# CampLight.net
KiCad netlist of a schematic drawn in EAGLE
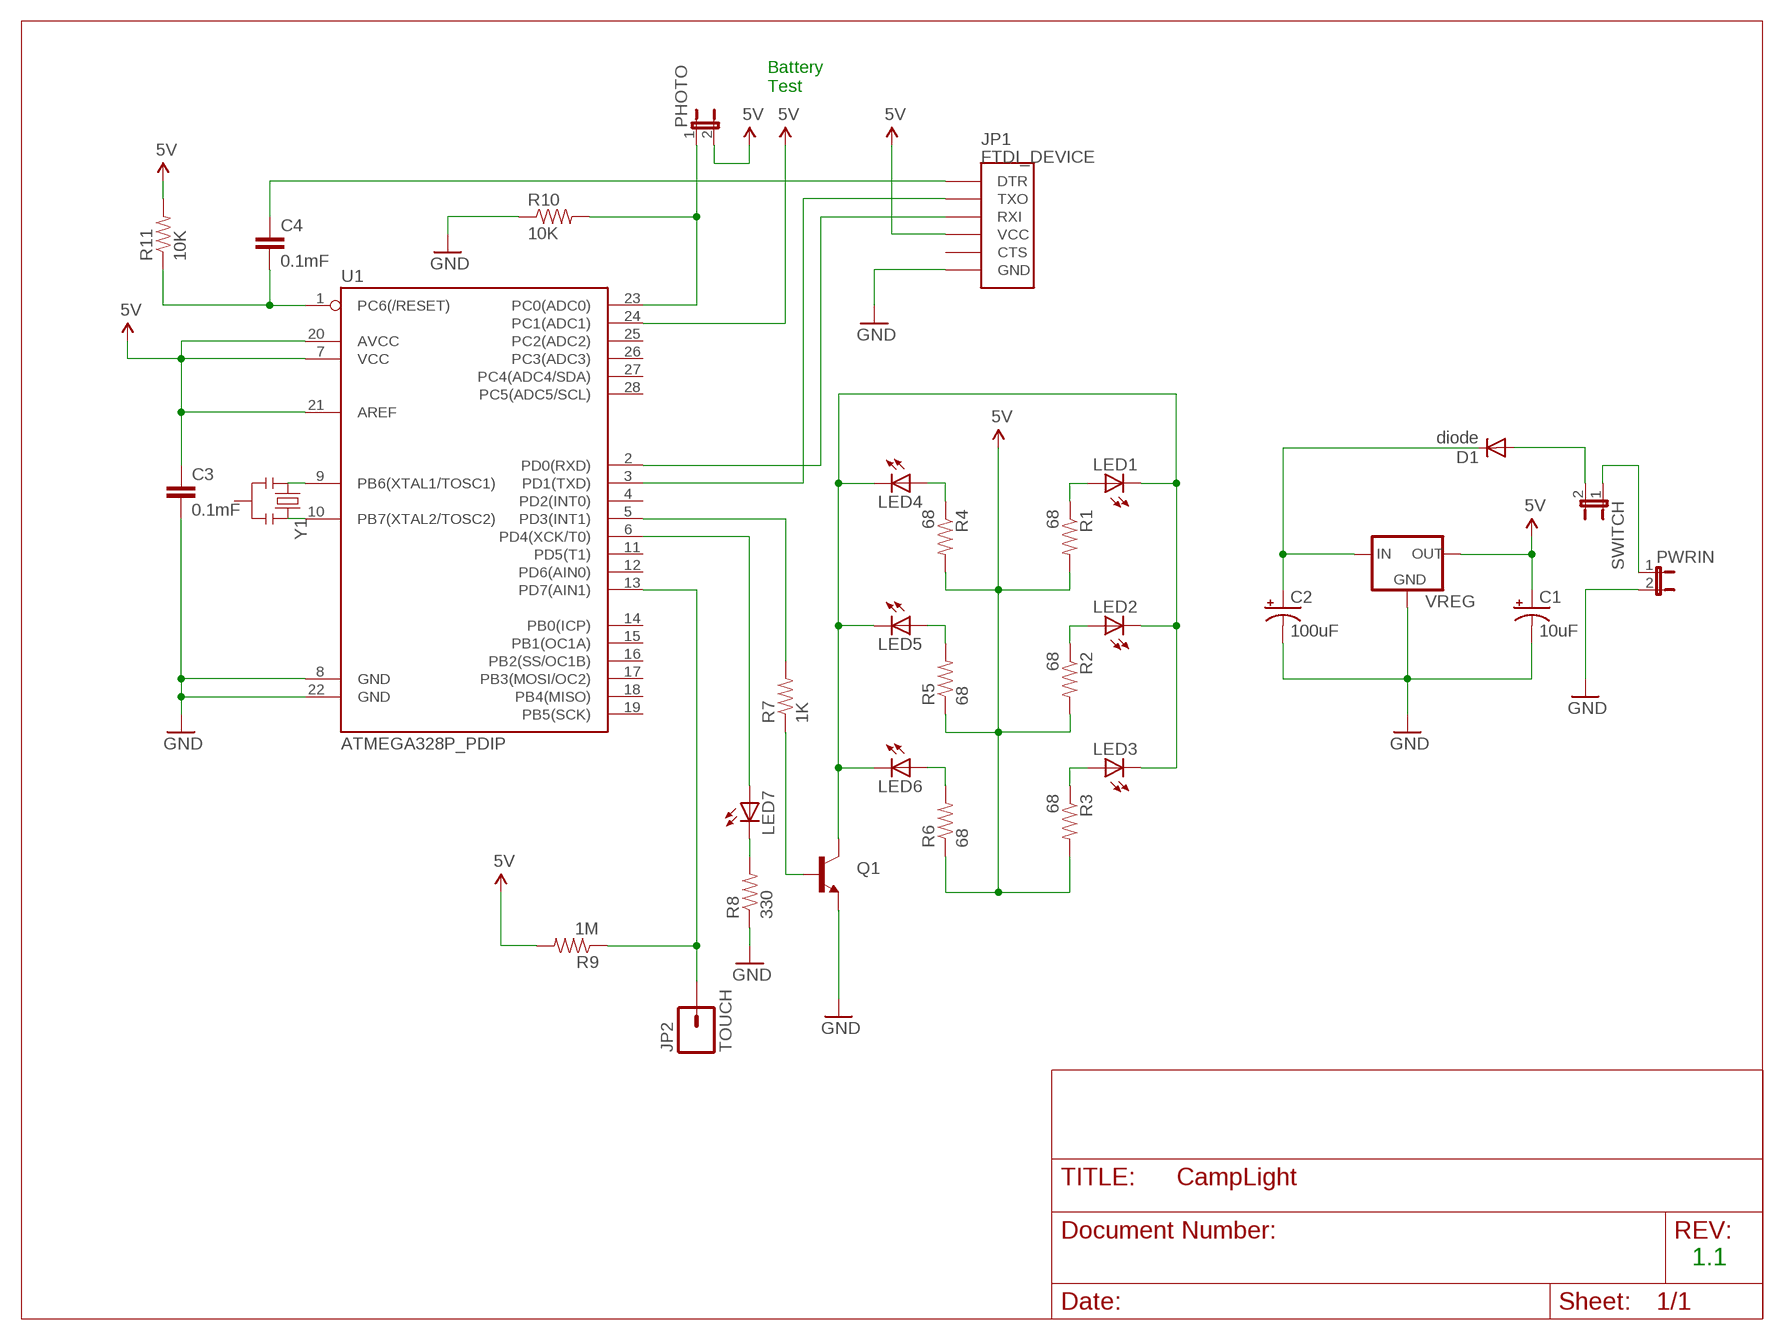
[diagram p0: schematic, sheet 1]

(export (version "E")
  (design (tool "Eeschema 10.0.6"))
  (components
    (comp (ref "C1")
      (value "10uF")
      (footprint "eagle-import:CPOL-RADIAL-10UF-25V")
      (libsource (lib "eagle-import") (part "CAP_POLPTH2"))
    )
    (comp (ref "C2")
      (value "100uF")
      (footprint "eagle-import:CPOL-RADIAL-10UF-25V")
      (libsource (lib "eagle-import") (part "CAP_POLPTH2"))
    )
    (comp (ref "C3")
      (value "0.1mF")
      (footprint "eagle-import:CAP-PTH-SMALL")
      (libsource (lib "eagle-import") (part "CAPPTH"))
    )
    (comp (ref "C4")
      (value "0.1mF")
      (footprint "eagle-import:CAP-PTH-SMALL")
      (libsource (lib "eagle-import") (part "CAPPTH"))
    )
    (comp (ref "D1")
      (value "diode")
      (footprint "eagle-import:DIODE-1N4001")
      (libsource (lib "eagle-import") (part "DIODEPTH"))
    )
    (comp (ref "JP1")
      (value "FTDI_DEVICE")
      (footprint "eagle-import:FTDI_DEVICE_SIDE")
      (libsource (lib "eagle-import") (part "FTDI_DEVICE"))
    )
    (comp (ref "JP2")
      (value "TOUCH")
      (footprint "eagle-import:1X01")
      (libsource (lib "eagle-import") (part "M01PTH"))
    )
    (comp (ref "LED1")
      (value "LED5MM")
      (footprint "eagle-import:LED5MM")
      (libsource (lib "eagle-import") (part "LED5MM"))
    )
    (comp (ref "LED2")
      (value "LED5MM")
      (footprint "eagle-import:LED5MM")
      (libsource (lib "eagle-import") (part "LED5MM"))
    )
    (comp (ref "LED3")
      (value "LED5MM")
      (footprint "eagle-import:LED5MM")
      (libsource (lib "eagle-import") (part "LED5MM"))
    )
    (comp (ref "LED4")
      (value "LED5MM")
      (footprint "eagle-import:LED5MM")
      (libsource (lib "eagle-import") (part "LED5MM"))
    )
    (comp (ref "LED5")
      (value "LED5MM")
      (footprint "eagle-import:LED5MM")
      (libsource (lib "eagle-import") (part "LED5MM"))
    )
    (comp (ref "LED6")
      (value "LED5MM")
      (footprint "eagle-import:LED5MM")
      (libsource (lib "eagle-import") (part "LED5MM"))
    )
    (comp (ref "LED7")
      (value "LED3MM")
      (footprint "eagle-import:LED3MM")
      (libsource (lib "eagle-import") (part "LED3MM"))
    )
    (comp (ref "PHOTO")
      (value "JUMPER-2PTH_LOCK")
      (footprint "eagle-import:1X02_LOCK")
      (libsource (lib "eagle-import") (part "JUMPER-2PTH_LOCK"))
    )
    (comp (ref "PWRIN")
      (value "JUMPER-2PTH_LOCK")
      (footprint "eagle-import:1X02_LOCK")
      (libsource (lib "eagle-import") (part "JUMPER-2PTH_LOCK"))
    )
    (comp (ref "Q1")
      (value "TRANSISTOR_NPNTO-92-AMMO")
      (footprint "eagle-import:TO-92-AMMO")
      (libsource (lib "eagle-import") (part "TRANSISTOR_NPNTO-92-AMMO"))
    )
    (comp (ref "R1")
      (value "68")
      (footprint "eagle-import:AXIAL-0.3")
      (libsource (lib "eagle-import") (part "SparkFun-Resistors_RESISTORAXIAL-0.3"))
    )
    (comp (ref "R2")
      (value "68")
      (footprint "eagle-import:AXIAL-0.3")
      (libsource (lib "eagle-import") (part "SparkFun-Resistors_RESISTORAXIAL-0.3"))
    )
    (comp (ref "R3")
      (value "68")
      (footprint "eagle-import:AXIAL-0.3")
      (libsource (lib "eagle-import") (part "SparkFun-Resistors_RESISTORAXIAL-0.3"))
    )
    (comp (ref "R4")
      (value "68")
      (footprint "eagle-import:AXIAL-0.3")
      (libsource (lib "eagle-import") (part "SparkFun-Resistors_RESISTORAXIAL-0.3"))
    )
    (comp (ref "R5")
      (value "68")
      (footprint "eagle-import:AXIAL-0.3")
      (libsource (lib "eagle-import") (part "SparkFun-Resistors_RESISTORAXIAL-0.3"))
    )
    (comp (ref "R6")
      (value "68")
      (footprint "eagle-import:AXIAL-0.3")
      (libsource (lib "eagle-import") (part "SparkFun-Resistors_RESISTORAXIAL-0.3"))
    )
    (comp (ref "R7")
      (value "1K")
      (footprint "eagle-import:AXIAL-0.4")
      (libsource (lib "eagle-import") (part "RESISTORPTH-1/4W"))
    )
    (comp (ref "R8")
      (value "330")
      (footprint "eagle-import:AXIAL-0.3")
      (libsource (lib "eagle-import") (part "SparkFun-Resistors_RESISTORAXIAL-0.3"))
    )
    (comp (ref "R9")
      (value "1M")
      (footprint "eagle-import:AXIAL-0.4")
      (libsource (lib "eagle-import") (part "RESISTORPTH-1/4W"))
    )
    (comp (ref "R10")
      (value "10K")
      (footprint "eagle-import:AXIAL-0.3")
      (libsource (lib "eagle-import") (part "SparkFun-Resistors_RESISTORAXIAL-0.3"))
    )
    (comp (ref "R11")
      (value "10K")
      (footprint "eagle-import:AXIAL-0.3")
      (libsource (lib "eagle-import") (part "SparkFun-Resistors_RESISTORAXIAL-0.3"))
    )
    (comp (ref "SWITCH")
      (value "JUMPER-2PTH_LOCK")
      (footprint "eagle-import:1X02_LOCK")
      (libsource (lib "eagle-import") (part "JUMPER-2PTH_LOCK"))
    )
    (comp (ref "U1")
      (value "ATMEGA328P_PDIP")
      (footprint "eagle-import:DIL28-3")
      (libsource (lib "eagle-import") (part "ATMEGA328P_PDIP"))
    )
    (comp (ref "VREG")
      (value "78LXX")
      (footprint "eagle-import:78LXX")
      (libsource (lib "eagle-import") (part "78LXX"))
    )
    (comp (ref "Y1")
      (value "RESONATORPTH")
      (footprint "eagle-import:RESONATOR-PTH")
      (libsource (lib "eagle-import") (part "RESONATORPTH"))
    )
  )
  (nets
    (net (code "1") (name "5V") (class "Default")
      (node (ref "C1") (pin "1") (pinfunction "+_1") (pintype "passive"))
      (node (ref "C3") (pin "1") (pinfunction "1_1") (pintype "passive"))
      (node (ref "JP1") (pin "P$4") (pinfunction "VCC_P$4") (pintype "bidirectional"))
      (node (ref "PHOTO") (pin "2") (pinfunction "2_2") (pintype "passive"))
      (node (ref "R1") (pin "P$2") (pinfunction "2_P$2") (pintype "passive"))
      (node (ref "R11") (pin "P$2") (pinfunction "2_P$2") (pintype "passive"))
      (node (ref "R2") (pin "P$2") (pinfunction "2_P$2") (pintype "passive"))
      (node (ref "R3") (pin "P$2") (pinfunction "2_P$2") (pintype "passive"))
      (node (ref "R4") (pin "P$2") (pinfunction "2_P$2") (pintype "passive"))
      (node (ref "R5") (pin "P$1") (pinfunction "1_P$1") (pintype "passive"))
      (node (ref "R6") (pin "P$1") (pinfunction "1_P$1") (pintype "passive"))
      (node (ref "R9") (pin "P$2") (pinfunction "2_P$2") (pintype "passive"))
      (node (ref "U1") (pin "20") (pinfunction "AVCC_20") (pintype "bidirectional"))
      (node (ref "U1") (pin "21") (pinfunction "AREF_21") (pintype "bidirectional"))
      (node (ref "U1") (pin "24") (pinfunction "PC1(ADC1)_24") (pintype "bidirectional"))
      (node (ref "U1") (pin "7") (pinfunction "VCC_7") (pintype "bidirectional"))
      (node (ref "VREG") (pin "OUT") (pinfunction "OUT_OUT") (pintype "passive"))
    )
    (net (code "2") (name "GND") (class "Default")
      (node (ref "C1") (pin "2") (pinfunction "-_2") (pintype "passive"))
      (node (ref "C2") (pin "2") (pinfunction "-_2") (pintype "passive"))
      (node (ref "C3") (pin "2") (pinfunction "2_2") (pintype "passive"))
      (node (ref "JP1") (pin "P$6") (pinfunction "GND_P$6") (pintype "bidirectional"))
      (node (ref "PWRIN") (pin "2") (pinfunction "2_2") (pintype "passive"))
      (node (ref "Q1") (pin "1") (pinfunction "E_1") (pintype "passive"))
      (node (ref "R10") (pin "P$1") (pinfunction "1_P$1") (pintype "passive"))
      (node (ref "R8") (pin "P$1") (pinfunction "1_P$1") (pintype "passive"))
      (node (ref "U1") (pin "22") (pinfunction "GND_22") (pintype "bidirectional"))
      (node (ref "U1") (pin "8") (pinfunction "GND_8") (pintype "bidirectional"))
      (node (ref "VREG") (pin "GND") (pinfunction "GND_GND") (pintype "input"))
    )
    (net (code "3") (name "Net-(C2-+)") (class "Default")
      (node (ref "C2") (pin "1") (pinfunction "+_1") (pintype "passive"))
      (node (ref "D1") (pin "C") (pinfunction "C_C") (pintype "passive"))
      (node (ref "VREG") (pin "IN") (pinfunction "IN_IN") (pintype "input"))
    )
    (net (code "4") (name "Net-(D1-PadA)") (class "Default")
      (node (ref "D1") (pin "A") (pinfunction "A_A") (pintype "passive"))
      (node (ref "SWITCH") (pin "2") (pinfunction "2_2") (pintype "passive"))
    )
    (net (code "5") (name "Net-(JP1-DTR)") (class "Default")
      (node (ref "C4") (pin "1") (pinfunction "1_1") (pintype "passive"))
      (node (ref "JP1") (pin "P$1") (pinfunction "DTR_P$1") (pintype "bidirectional"))
    )
    (net (code "6") (name "Net-(JP1-RXI)") (class "Default")
      (node (ref "JP1") (pin "P$3") (pinfunction "RXI_P$3") (pintype "bidirectional"))
      (node (ref "U1") (pin "2") (pinfunction "PD0(RXD)_2") (pintype "bidirectional"))
    )
    (net (code "7") (name "Net-(JP1-TXO)") (class "Default")
      (node (ref "JP1") (pin "P$2") (pinfunction "TXO_P$2") (pintype "bidirectional"))
      (node (ref "U1") (pin "3") (pinfunction "PD1(TXD)_3") (pintype "bidirectional"))
    )
    (net (code "8") (name "Net-(LED1-C)") (class "Default")
      (node (ref "LED1") (pin "K") (pinfunction "C_K") (pintype "passive"))
      (node (ref "LED2") (pin "K") (pinfunction "C_K") (pintype "passive"))
      (node (ref "LED3") (pin "K") (pinfunction "C_K") (pintype "passive"))
      (node (ref "LED4") (pin "K") (pinfunction "C_K") (pintype "passive"))
      (node (ref "LED5") (pin "K") (pinfunction "C_K") (pintype "passive"))
      (node (ref "LED6") (pin "K") (pinfunction "C_K") (pintype "passive"))
      (node (ref "Q1") (pin "3") (pinfunction "C_3") (pintype "passive"))
    )
    (net (code "9") (name "Net-(LED7-C)") (class "Default")
      (node (ref "LED7") (pin "K") (pinfunction "C_K") (pintype "passive"))
      (node (ref "R8") (pin "P$2") (pinfunction "2_P$2") (pintype "passive"))
    )
    (net (code "10") (name "Net-(PWRIN-Pad1)") (class "Default")
      (node (ref "PWRIN") (pin "1") (pinfunction "1_1") (pintype "passive"))
      (node (ref "SWITCH") (pin "1") (pinfunction "1_1") (pintype "passive"))
    )
    (net (code "11") (name "Net-(Q1-B)") (class "Default")
      (node (ref "Q1") (pin "2") (pinfunction "B_2") (pintype "passive"))
      (node (ref "R7") (pin "P$1") (pinfunction "1_P$1") (pintype "passive"))
    )
    (net (code "12") (name "Net-(R1-1)") (class "Default")
      (node (ref "LED1") (pin "A") (pinfunction "A_A") (pintype "passive"))
      (node (ref "R1") (pin "P$1") (pinfunction "1_P$1") (pintype "passive"))
    )
    (net (code "13") (name "Net-(R2-1)") (class "Default")
      (node (ref "LED2") (pin "A") (pinfunction "A_A") (pintype "passive"))
      (node (ref "R2") (pin "P$1") (pinfunction "1_P$1") (pintype "passive"))
    )
    (net (code "14") (name "Net-(R3-1)") (class "Default")
      (node (ref "LED3") (pin "A") (pinfunction "A_A") (pintype "passive"))
      (node (ref "R3") (pin "P$1") (pinfunction "1_P$1") (pintype "passive"))
    )
    (net (code "15") (name "Net-(R4-1)") (class "Default")
      (node (ref "LED4") (pin "A") (pinfunction "A_A") (pintype "passive"))
      (node (ref "R4") (pin "P$1") (pinfunction "1_P$1") (pintype "passive"))
    )
    (net (code "16") (name "Net-(R5-2)") (class "Default")
      (node (ref "LED5") (pin "A") (pinfunction "A_A") (pintype "passive"))
      (node (ref "R5") (pin "P$2") (pinfunction "2_P$2") (pintype "passive"))
    )
    (net (code "17") (name "Net-(R6-2)") (class "Default")
      (node (ref "LED6") (pin "A") (pinfunction "A_A") (pintype "passive"))
      (node (ref "R6") (pin "P$2") (pinfunction "2_P$2") (pintype "passive"))
    )
    (net (code "18") (name "Net-(R7-2)") (class "Default")
      (node (ref "R7") (pin "P$2") (pinfunction "2_P$2") (pintype "passive"))
      (node (ref "U1") (pin "5") (pinfunction "PD3(INT1)_5") (pintype "bidirectional"))
    )
    (net (code "19") (name "Net-(R9-1)") (class "Default")
      (node (ref "JP2") (pin "1") (pinfunction "1_1") (pintype "passive"))
      (node (ref "R9") (pin "P$1") (pinfunction "1_P$1") (pintype "passive"))
      (node (ref "U1") (pin "13") (pinfunction "PD7(AIN1)_13") (pintype "bidirectional"))
    )
    (net (code "20") (name "Net-(R10-2)") (class "Default")
      (node (ref "PHOTO") (pin "1") (pinfunction "1_1") (pintype "passive"))
      (node (ref "R10") (pin "P$2") (pinfunction "2_P$2") (pintype "passive"))
      (node (ref "U1") (pin "23") (pinfunction "PC0(ADC0)_23") (pintype "bidirectional"))
    )
    (net (code "21") (name "Net-(R11-1)") (class "Default")
      (node (ref "C4") (pin "2") (pinfunction "2_2") (pintype "passive"))
      (node (ref "R11") (pin "P$1") (pinfunction "1_P$1") (pintype "passive"))
      (node (ref "U1") (pin "1") (pinfunction "PC6(/RESET)_1") (pintype "bidirectional"))
    )
    (net (code "22") (name "Net-(U1-PB6(XTAL1{slash}TOSC1))") (class "Default")
      (node (ref "U1") (pin "9") (pinfunction "PB6(XTAL1/TOSC1)_9") (pintype "bidirectional"))
      (node (ref "Y1") (pin "1") (pinfunction "1_1") (pintype "passive"))
    )
    (net (code "23") (name "Net-(U1-PB7(XTAL2{slash}TOSC2))") (class "Default")
      (node (ref "U1") (pin "10") (pinfunction "PB7(XTAL2/TOSC2)_10") (pintype "bidirectional"))
      (node (ref "Y1") (pin "3") (pinfunction "3_3") (pintype "passive"))
    )
    (net (code "24") (name "Net-(U1-PD4(XCK{slash}T0))") (class "Default")
      (node (ref "LED7") (pin "A") (pinfunction "A_A") (pintype "passive"))
      (node (ref "U1") (pin "6") (pinfunction "PD4(XCK/T0)_6") (pintype "bidirectional"))
    )
    (net (code "25") (name "unconnected-(JP1-CTS-PadP$5)") (class "Default")
      (node (ref "JP1") (pin "P$5") (pinfunction "CTS_P$5") (pintype "bidirectional"))
    )
    (net (code "26") (name "unconnected-(U1-PB0(ICP)-Pad14)") (class "Default")
      (node (ref "U1") (pin "14") (pinfunction "PB0(ICP)_14") (pintype "bidirectional"))
    )
    (net (code "27") (name "unconnected-(U1-PB1(OC1A)-Pad15)") (class "Default")
      (node (ref "U1") (pin "15") (pinfunction "PB1(OC1A)_15") (pintype "bidirectional"))
    )
    (net (code "28") (name "unconnected-(U1-PB2(SS{slash}OC1B)-Pad16)") (class "Default")
      (node (ref "U1") (pin "16") (pinfunction "PB2(SS/OC1B)_16") (pintype "bidirectional"))
    )
    (net (code "29") (name "unconnected-(U1-PB3(MOSI{slash}OC2)-Pad17)") (class "Default")
      (node (ref "U1") (pin "17") (pinfunction "PB3(MOSI/OC2)_17") (pintype "bidirectional"))
    )
    (net (code "30") (name "unconnected-(U1-PB4(MISO)-Pad18)") (class "Default")
      (node (ref "U1") (pin "18") (pinfunction "PB4(MISO)_18") (pintype "bidirectional"))
    )
    (net (code "31") (name "unconnected-(U1-PB5(SCK)-Pad19)") (class "Default")
      (node (ref "U1") (pin "19") (pinfunction "PB5(SCK)_19") (pintype "bidirectional"))
    )
    (net (code "32") (name "unconnected-(U1-PC2(ADC2)-Pad25)") (class "Default")
      (node (ref "U1") (pin "25") (pinfunction "PC2(ADC2)_25") (pintype "bidirectional"))
    )
    (net (code "33") (name "unconnected-(U1-PC3(ADC3)-Pad26)") (class "Default")
      (node (ref "U1") (pin "26") (pinfunction "PC3(ADC3)_26") (pintype "bidirectional"))
    )
    (net (code "34") (name "unconnected-(U1-PC4(ADC4{slash}SDA)-Pad27)") (class "Default")
      (node (ref "U1") (pin "27") (pinfunction "PC4(ADC4/SDA)_27") (pintype "bidirectional"))
    )
    (net (code "35") (name "unconnected-(U1-PC5(ADC5{slash}SCL)-Pad28)") (class "Default")
      (node (ref "U1") (pin "28") (pinfunction "PC5(ADC5/SCL)_28") (pintype "bidirectional"))
    )
    (net (code "36") (name "unconnected-(U1-PD2(INT0)-Pad4)") (class "Default")
      (node (ref "U1") (pin "4") (pinfunction "PD2(INT0)_4") (pintype "bidirectional"))
    )
    (net (code "37") (name "unconnected-(U1-PD5(T1)-Pad11)") (class "Default")
      (node (ref "U1") (pin "11") (pinfunction "PD5(T1)_11") (pintype "bidirectional"))
    )
    (net (code "38") (name "unconnected-(U1-PD6(AIN0)-Pad12)") (class "Default")
      (node (ref "U1") (pin "12") (pinfunction "PD6(AIN0)_12") (pintype "bidirectional"))
    )
    (net (code "39") (name "unconnected-(Y1-Pad2)") (class "Default")
      (node (ref "Y1") (pin "2") (pinfunction "2_2") (pintype "passive"))
    )
  )
)
